# logRTC.net
KiCad netlist of a schematic drawn in Altium Designer
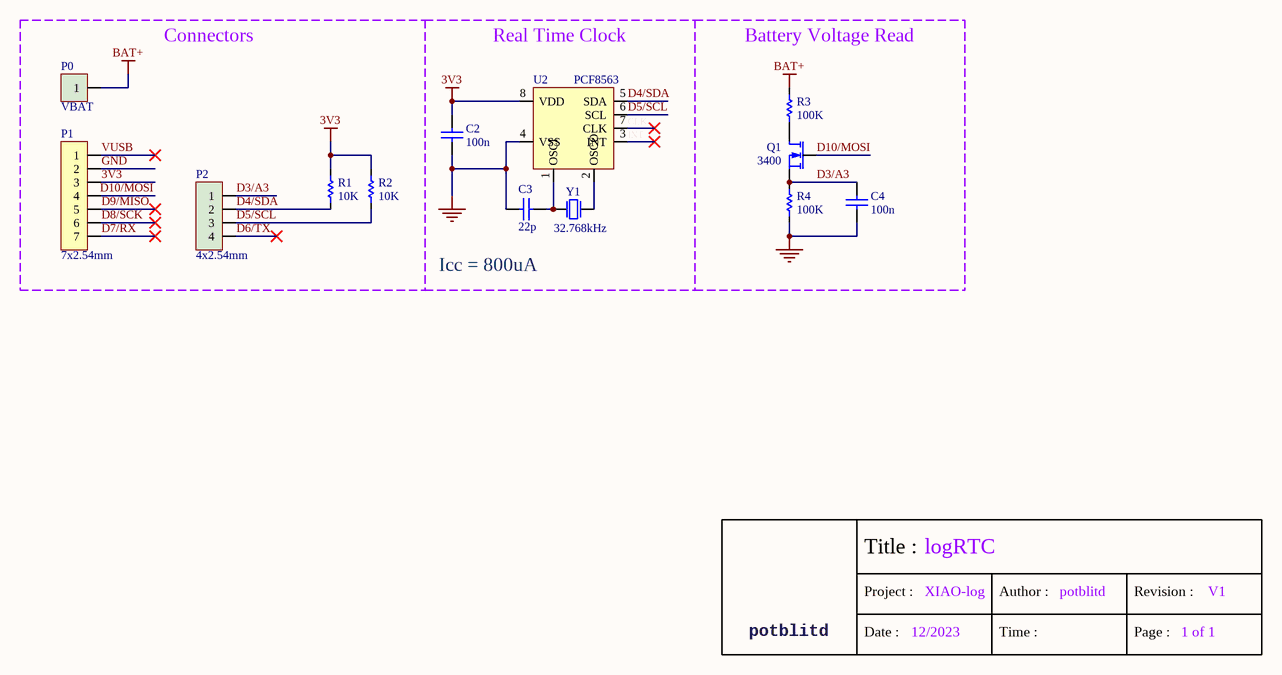
[diagram p0: logRTC.SchDoc]

(export (version "E")
  (design (tool "Eeschema 10.0.6"))
  (components
    (comp (ref "C2")
      (value "100n")
      (footprint "0603CM")
      (description "Capacitor 100nF ±10% 50V")
      (fields (field (name "Comment") "Capacitor"))
      (libsource (lib "Simulation Generic Components") (part "Capacitor"))
    )
    (comp (ref "C3")
      (value "22p")
      (footprint "0603CM")
      (description "Capacitor 22pF ±5% 50V")
      (fields (field (name "Comment") "Capacitor"))
      (libsource (lib "Simulation Generic Components") (part "Capacitor"))
    )
    (comp (ref "C4")
      (value "100n")
      (footprint "0603CM")
      (description "Capacitor 100nF ±10% 50V")
      (fields (field (name "Comment") "Capacitor"))
      (libsource (lib "Simulation Generic Components") (part "Capacitor"))
    )
    (comp (ref "P0")
      (value "VBAT")
      (footprint "XIAO-BATCON")
      (description "BAT+ special pin")
      (libsource (lib "AltiumLib") (part "1-pin Header"))
    )
    (comp (ref "P1")
      (value "7x2.54mm")
      (footprint "7P-2.54mm-EDGE")
      (description "General 7-pin connection")
      (libsource (lib "AltiumLib") (part "7-pins Header"))
    )
    (comp (ref "P2")
      (value "4x2.54mm")
      (footprint "4P-2.54mm-EDGE")
      (description "General 4-pin connection")
      (libsource (lib "AltiumLib") (part "4-pins Header"))
    )
    (comp (ref "Q1")
      (value "3400")
      (footprint "SOT23-3 M")
      (description "MOSFET N-channel 30V 5.7A")
      (libsource (lib "AltiumLib") (part "MOSFET-N"))
    )
    (comp (ref "R1")
      (value "10K")
      (footprint "0603RM")
      (description "Resistor 10kΩ ±1% 100mW")
      (fields (field (name "Comment") "Resistor"))
      (libsource (lib "Simulation Generic Components") (part "RES"))
    )
    (comp (ref "R2")
      (value "10K")
      (footprint "0603RM")
      (description "Resistor 10kΩ ±1% 100mW")
      (fields (field (name "Comment") "Resistor"))
      (libsource (lib "Simulation Generic Components") (part "RES"))
    )
    (comp (ref "R3")
      (value "100K")
      (footprint "0603RM")
      (description "Resistor 100kΩ ±1% 100mW")
      (fields (field (name "Comment") "Resistor"))
      (libsource (lib "Simulation Generic Components") (part "RES"))
    )
    (comp (ref "R4")
      (value "100K")
      (footprint "0603RM")
      (description "Resistor 100kΩ ±1% 100mW")
      (fields (field (name "Comment") "Resistor"))
      (libsource (lib "Simulation Generic Components") (part "RES"))
    )
    (comp (ref "U2")
      (value "PCF8563")
      (footprint "SOP-8 M")
      (description "IC real-time clock with alarm interrupt")
      (libsource (lib "AltiumLib") (part "RTC-8563"))
    )
    (comp (ref "Y1")
      (value "32.768kHz")
      (footprint "FC135 M")
      (description "Crystal oscillator 32.768kHz 20ppm 12.5pF")
      (fields (field (name "Comment") "Oscillator"))
      (libsource (lib "AltiumLib") (part "XO-2"))
    )
  )
  (nets
    (net (code "1") (name "/CLK") (class "Default")
      (node (ref "U2") (pin "7") (pinfunction "CLK_7") (pintype "passive+no_connect"))
    )
    (net (code "2") (name "/D3{slash}A3") (class "Default")
      (node (ref "C4") (pin "1") (pinfunction "1_1") (pintype "passive"))
      (node (ref "P2") (pin "1") (pinfunction "1_1") (pintype "passive"))
      (node (ref "Q1") (pin "2") (pinfunction "S_2") (pintype "passive"))
      (node (ref "R4") (pin "2") (pinfunction "2_2") (pintype "passive"))
    )
    (net (code "3") (name "/D4{slash}SDA") (class "Default")
      (node (ref "P2") (pin "2") (pinfunction "2_2") (pintype "passive"))
      (node (ref "R1") (pin "1") (pinfunction "1_1") (pintype "passive"))
      (node (ref "U2") (pin "5") (pinfunction "SDA_5") (pintype "passive"))
    )
    (net (code "4") (name "/D5{slash}SCL") (class "Default")
      (node (ref "P2") (pin "3") (pinfunction "3_3") (pintype "passive"))
      (node (ref "R2") (pin "1") (pinfunction "1_1") (pintype "passive"))
      (node (ref "U2") (pin "6") (pinfunction "SCL_6") (pintype "passive"))
    )
    (net (code "5") (name "/D6{slash}TX") (class "Default")
      (node (ref "P2") (pin "4") (pinfunction "4_4") (pintype "passive+no_connect"))
    )
    (net (code "6") (name "/D7{slash}RX") (class "Default")
      (node (ref "P1") (pin "7") (pinfunction "7_7") (pintype "passive+no_connect"))
    )
    (net (code "7") (name "/D8{slash}SCK") (class "Default")
      (node (ref "P1") (pin "6") (pinfunction "6_6") (pintype "passive+no_connect"))
    )
    (net (code "8") (name "/D9{slash}MISO") (class "Default")
      (node (ref "P1") (pin "5") (pinfunction "5_5") (pintype "passive+no_connect"))
    )
    (net (code "9") (name "/D10{slash}MOSI") (class "Default")
      (node (ref "P1") (pin "4") (pinfunction "4_4") (pintype "passive"))
      (node (ref "Q1") (pin "1") (pinfunction "G_1") (pintype "passive"))
    )
    (net (code "10") (name "/INT") (class "Default")
      (node (ref "U2") (pin "3") (pinfunction "INT_3") (pintype "passive+no_connect"))
    )
    (net (code "11") (name "/VUSB") (class "Default")
      (node (ref "P1") (pin "1") (pinfunction "1_1") (pintype "passive+no_connect"))
    )
    (net (code "12") (name "3V3") (class "Default")
      (node (ref "C2") (pin "1") (pinfunction "1_1") (pintype "passive"))
      (node (ref "P1") (pin "3") (pinfunction "3_3") (pintype "passive"))
      (node (ref "R1") (pin "2") (pinfunction "2_2") (pintype "passive"))
      (node (ref "R2") (pin "2") (pinfunction "2_2") (pintype "passive"))
      (node (ref "U2") (pin "8") (pinfunction "VDD_8") (pintype "passive"))
    )
    (net (code "13") (name "BAT+") (class "Default")
      (node (ref "P0") (pin "1") (pinfunction "1_1") (pintype "passive"))
      (node (ref "R3") (pin "2") (pinfunction "2_2") (pintype "passive"))
    )
    (net (code "14") (name "GND") (class "Default")
      (node (ref "C2") (pin "2") (pinfunction "2_2") (pintype "passive"))
      (node (ref "C3") (pin "2") (pinfunction "2_2") (pintype "passive"))
      (node (ref "C4") (pin "2") (pinfunction "2_2") (pintype "passive"))
      (node (ref "P1") (pin "2") (pinfunction "2_2") (pintype "passive"))
      (node (ref "R4") (pin "1") (pinfunction "1_1") (pintype "passive"))
      (node (ref "U2") (pin "4") (pinfunction "VSS_4") (pintype "passive"))
    )
    (net (code "15") (name "Net-(Q1-D)") (class "Default")
      (node (ref "Q1") (pin "3") (pinfunction "D_3") (pintype "passive"))
      (node (ref "R3") (pin "1") (pinfunction "1_1") (pintype "passive"))
    )
    (net (code "16") (name "Net-(U2-OSCI)") (class "Default")
      (node (ref "C3") (pin "1") (pinfunction "1_1") (pintype "passive"))
      (node (ref "U2") (pin "1") (pinfunction "OSCI_1") (pintype "passive"))
      (node (ref "Y1") (pin "2") (pinfunction "2_2") (pintype "passive"))
    )
    (net (code "17") (name "Net-(U2-OSCO)") (class "Default")
      (node (ref "U2") (pin "2") (pinfunction "OSCO_2") (pintype "passive"))
      (node (ref "Y1") (pin "1") (pinfunction "1_1") (pintype "passive"))
    )
  )
)
